# knobtester.net
KiCad netlist of a schematic drawn in EAGLE
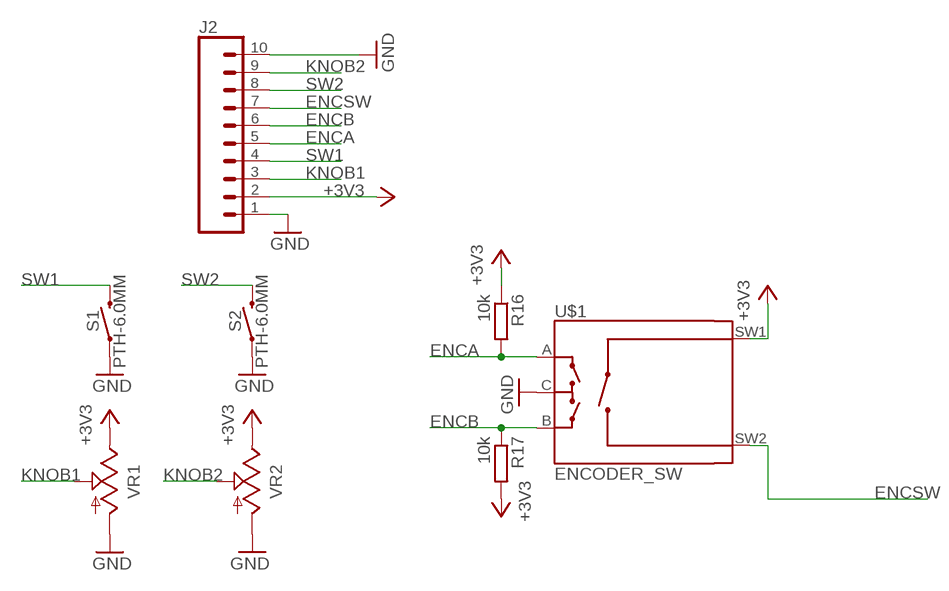
[diagram p0: schematic, sheet 1]

(export (version "E")
  (design (tool "Eeschema 10.0.6"))
  (components
    (comp (ref "J2")
      (value "CONN_10\"")
      (footprint "eagle-import:1X10")
      (libsource (lib "eagle-import") (part "CONN_10{dblquote}"))
    )
    (comp (ref "R16")
      (value "10k")
      (footprint "eagle-import:R0603")
      (libsource (lib "eagle-import") (part "R-EU_R0603"))
    )
    (comp (ref "R17")
      (value "10k")
      (footprint "eagle-import:R0603")
      (libsource (lib "eagle-import") (part "R-EU_R0603"))
    )
    (comp (ref "S1")
      (value "PTH-6.0MM")
      (footprint "eagle-import:TACTILE_SWITCH_PTH_6.0MM")
      (libsource (lib "eagle-import") (part "MOMENTARY-SWITCH-SPST-PTH-6.0MM"))
    )
    (comp (ref "S2")
      (value "PTH-6.0MM")
      (footprint "eagle-import:TACTILE_SWITCH_PTH_6.0MM")
      (libsource (lib "eagle-import") (part "MOMENTARY-SWITCH-SPST-PTH-6.0MM"))
    )
    (comp (ref "U$1")
      (value "ENCODER_SW")
      (footprint "eagle-import:ENCODER_SW")
      (libsource (lib "eagle-import") (part "ENCODER_SW"))
    )
    (comp (ref "VR1")
      (value "9MM_SNAP-IN_POT_")
      (footprint "eagle-import:9MM_SNAP-IN_POT")
      (libsource (lib "eagle-import") (part "9MM_SNAP-IN_POT_"))
    )
    (comp (ref "VR2")
      (value "9MM_SNAP-IN_POT_")
      (footprint "eagle-import:9MM_SNAP-IN_POT")
      (libsource (lib "eagle-import") (part "9MM_SNAP-IN_POT_"))
    )
  )
  (nets
    (net (code "1") (name "+3V3") (class "Default")
      (node (ref "J2") (pin "2") (pinfunction "2_2") (pintype "passive"))
      (node (ref "R16") (pin "1") (pinfunction "1_1") (pintype "passive"))
      (node (ref "R17") (pin "2") (pinfunction "2_2") (pintype "passive"))
      (node (ref "U$1") (pin "SW1") (pinfunction "SW1_SW1") (pintype "passive"))
      (node (ref "VR1") (pin "3") (pinfunction "E_3") (pintype "passive"))
      (node (ref "VR2") (pin "3") (pinfunction "E_3") (pintype "passive"))
    )
    (net (code "2") (name "/ENCA") (class "Default")
      (node (ref "J2") (pin "5") (pinfunction "5_5") (pintype "passive"))
      (node (ref "R16") (pin "2") (pinfunction "2_2") (pintype "passive"))
      (node (ref "U$1") (pin "A") (pinfunction "A_A") (pintype "bidirectional"))
    )
    (net (code "3") (name "/ENCB") (class "Default")
      (node (ref "J2") (pin "6") (pinfunction "6_6") (pintype "passive"))
      (node (ref "R17") (pin "1") (pinfunction "1_1") (pintype "passive"))
      (node (ref "U$1") (pin "B") (pinfunction "B_B") (pintype "bidirectional"))
    )
    (net (code "4") (name "/ENCSW") (class "Default")
      (node (ref "J2") (pin "7") (pinfunction "7_7") (pintype "passive"))
      (node (ref "U$1") (pin "SW2") (pinfunction "SW2_SW2") (pintype "passive"))
    )
    (net (code "5") (name "/KNOB1") (class "Default")
      (node (ref "J2") (pin "3") (pinfunction "3_3") (pintype "passive"))
      (node (ref "VR1") (pin "2") (pinfunction "S_2") (pintype "passive"))
    )
    (net (code "6") (name "/KNOB2") (class "Default")
      (node (ref "J2") (pin "9") (pinfunction "9_9") (pintype "passive"))
      (node (ref "VR2") (pin "2") (pinfunction "S_2") (pintype "passive"))
    )
    (net (code "7") (name "/SW1") (class "Default")
      (node (ref "J2") (pin "4") (pinfunction "4_4") (pintype "passive"))
      (node (ref "S1") (pin "3") (pinfunction "2_3") (pintype "passive"))
    )
    (net (code "8") (name "/SW2") (class "Default")
      (node (ref "J2") (pin "8") (pinfunction "8_8") (pintype "passive"))
      (node (ref "S2") (pin "3") (pinfunction "2_3") (pintype "passive"))
    )
    (net (code "9") (name "GND") (class "Default")
      (node (ref "J2") (pin "1") (pinfunction "1_1") (pintype "passive"))
      (node (ref "J2") (pin "10") (pinfunction "10_10") (pintype "passive"))
      (node (ref "S1") (pin "1") (pinfunction "1_1") (pintype "passive"))
      (node (ref "S2") (pin "1") (pinfunction "1_1") (pintype "passive"))
      (node (ref "U$1") (pin "C") (pinfunction "C_C") (pintype "bidirectional"))
      (node (ref "VR1") (pin "1") (pinfunction "A_1") (pintype "passive"))
      (node (ref "VR2") (pin "1") (pinfunction "A_1") (pintype "passive"))
    )
  )
)
